# Crystal_32MHz.net
KiCad netlist of a schematic drawn in Altium Designer
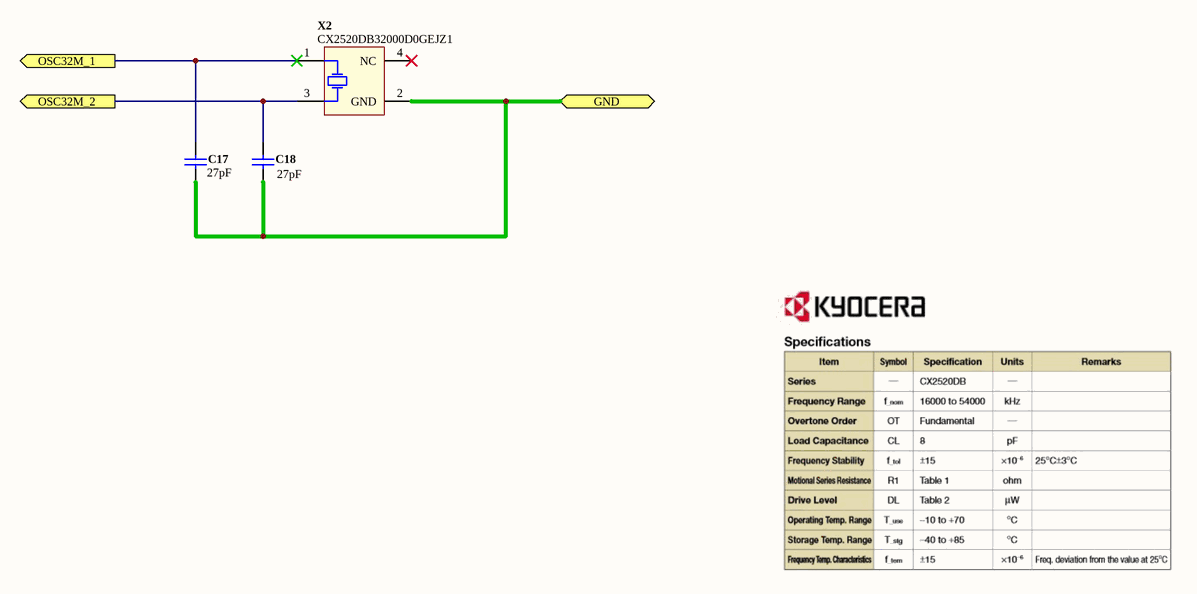
[diagram p0: Crystal_32MHz.SchDoc]

(export (version "E")
  (design (tool "Eeschema 10.0.6"))
  (components
    (comp (ref "C17")
      (value "27pF")
      (footprint "CAPC0402(1005)60_L")
      (description "CAP 27pF 16V ±1% 0402 (1005 Metric) Thickness 0.6mm SMD")
      (fields (field (name "TOLERANCE") "±1%") (field (name "Comment") "CAP 27pF 16V 0402(1005)"))
      (libsource (lib "Altium Content Vault") (part "CMP-1034-00950-1"))
    )
    (comp (ref "C18")
      (value "27pF")
      (footprint "CAPC0402(1005)60_L")
      (description "CAP 27pF 16V ±1% 0402 (1005 Metric) Thickness 0.6mm SMD")
      (fields (field (name "TOLERANCE") "±1%") (field (name "Comment") "CAP 27pF 16V 0402(1005)"))
      (libsource (lib "Altium Content Vault") (part "CMP-1034-00950-1"))
    )
    (comp (ref "X2")
      (value "CX2520DB32000D0GEJZ1")
      (footprint "AVX-CX2520DB32000D0GEJZ1-4_V")
      (description "Crystal, 32 MHz, 8 pF, -10 to 70 degC, Surface Mount 2.5 x 2.0 mm")
      (fields (field (name "MANUFACTURER") "Kyocera"))
      (libsource (lib "Altium Content Vault") (part "AVX-CX2520DB32000D0GEJZ1-4"))
    )
  )
  (nets
    (net (code "1") (name "/GND") (class "Default")
      (node (ref "C17") (pin "1") (pinfunction "1_1") (pintype "passive"))
      (node (ref "C18") (pin "1") (pinfunction "1_1") (pintype "passive"))
      (node (ref "X2") (pin "2") (pinfunction "GND_2") (pintype "power_in"))
    )
    (net (code "2") (name "/OSC32M_1") (class "Default")
      (node (ref "C17") (pin "2") (pinfunction "2_2") (pintype "passive"))
      (node (ref "X2") (pin "1") (pinfunction "HOT_1") (pintype "passive"))
    )
    (net (code "3") (name "/OSC32M_2") (class "Default")
      (node (ref "C18") (pin "2") (pinfunction "2_2") (pintype "passive"))
      (node (ref "X2") (pin "3") (pinfunction "HOT_3") (pintype "passive"))
    )
    (net (code "4") (name "unconnected-(X2-NC-Pad4)") (class "Default")
      (node (ref "X2") (pin "4") (pinfunction "NC_4") (pintype "passive+no_connect"))
    )
  )
)
